# SW_S_12.net
KiCad netlist of a schematic drawn in Altium Designer
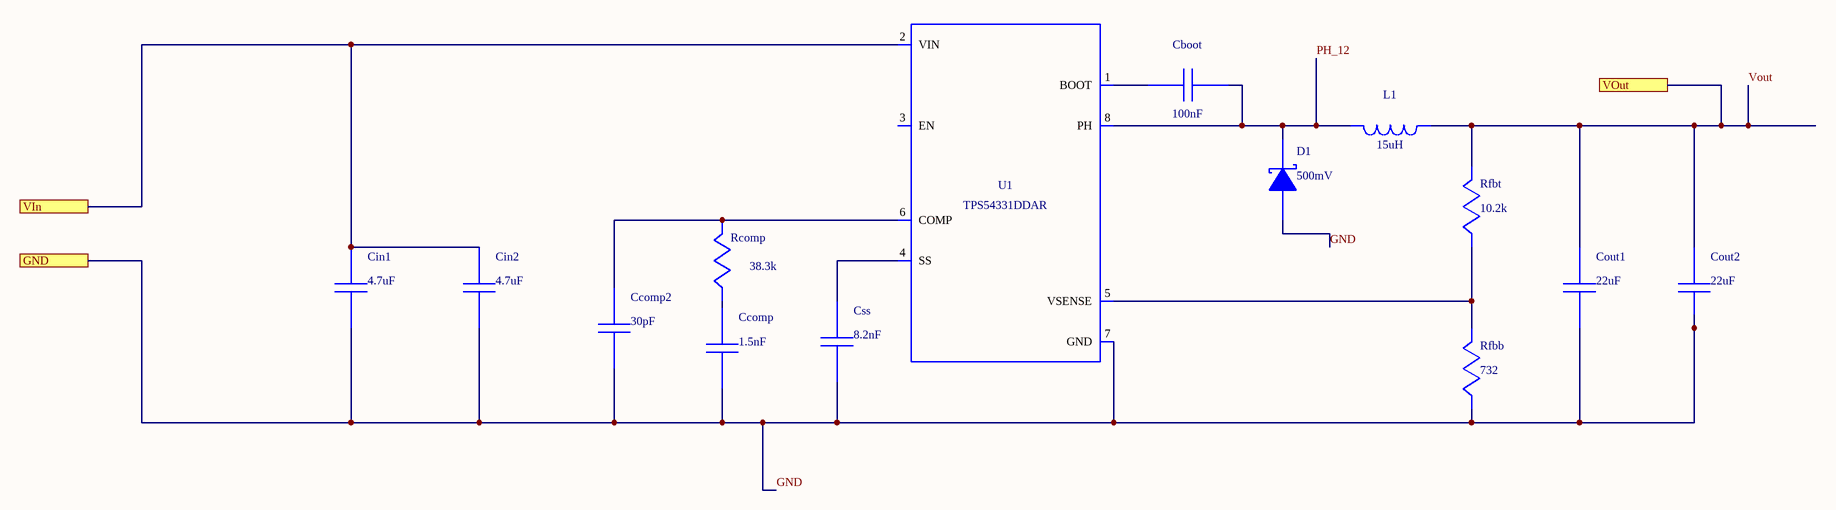
[diagram p0: SW_S_12.SchDoc]

(export (version "E")
  (design (tool "Eeschema 10.0.6"))
  (components
    (comp (ref "Cboot")
      (value "100nF")
      (footprint "1608[0603]")
      (description "C1608X7R1E104K")
      (libsource (lib "TI WEBENCH") (part "Cboot"))
    )
    (comp (ref "Ccomp")
      (value "1.5nF")
      (footprint "6-0805_M")
      (description "CC0805KRX7R9BB15")
      (fields (field (name "MANUFACTURER PART NUMBER") "CC0805KRX7R9BB152"))
      (libsource (lib "TI WEBENCH") (part "Ccomp"))
    )
    (comp (ref "Ccomp2")
      (value "30pF")
      (footprint "6-0805_M")
      (description "CL21C300JBANNNC")
      (libsource (lib "TI WEBENCH") (part "Ccomp2"))
    )
    (comp (ref "Cin1")
      (value "4.7uF")
      (footprint "C1210_M")
      (description "GRM32ER71H475KA8")
      (fields (field (name "MANUFACTURER PART NUMBER") "GRM32ER71H475KA88L"))
      (libsource (lib "TI WEBENCH") (part "Cin"))
    )
    (comp (ref "Cin2")
      (value "4.7uF")
      (footprint "C1210_M")
      (description "GRM32ER71H475KA8")
      (fields (field (name "MANUFACTURER PART NUMBER") "GRM32ER71H475KA88L"))
      (libsource (lib "TI WEBENCH") (part "Cin"))
    )
    (comp (ref "Cout1")
      (value "22uF")
      (footprint "C1210_M")
      (description "GRM32ER61E226KE1")
      (fields (field (name "MANUFACTURER PART NUMBER") "GRM32ER61E226KE15L"))
      (libsource (lib "TI WEBENCH") (part "Cout"))
    )
    (comp (ref "Cout2")
      (value "22uF")
      (footprint "C1210_M")
      (description "GRM32ER61E226KE1")
      (fields (field (name "MANUFACTURER PART NUMBER") "GRM32ER61E226KE15L"))
      (libsource (lib "TI WEBENCH") (part "Cout"))
    )
    (comp (ref "Css")
      (value "8.2nF")
      (footprint "1608[0603]")
      (description "GRM188R71E822KA0")
      (fields (field (name "MANUFACTURER PART NUMBER") "GRM188R71E822KA01D"))
      (libsource (lib "TI WEBENCH") (part "Css"))
    )
    (comp (ref "D1")
      (value "500mV")
      (footprint "SMA Diode Package")
      (description "B340A-13-F")
      (libsource (lib "TI WEBENCH") (part "D1"))
    )
    (comp (ref "L1")
      (value "15uH")
      (footprint "SRR1260")
      (description "SRR1260-150M")
      (libsource (lib "TI WEBENCH") (part "L1"))
    )
    (comp (ref "Rcomp")
      (value "38.3k")
      (footprint "6-0805_M")
      (description "CRCW080538K3FKEA")
      (libsource (lib "TI WEBENCH") (part "Rcomp"))
    )
    (comp (ref "Rfbb")
      (value "732")
      (footprint "6-0805_M")
      (description "CRCW0805732RFKEA")
      (libsource (lib "TI WEBENCH") (part "Rfbb"))
    )
    (comp (ref "Rfbt")
      (value "10.2k")
      (footprint "6-0805_M")
      (description "CRCW080510K2FKEA")
      (libsource (lib "TI WEBENCH") (part "Rfbt"))
    )
    (comp (ref "U1")
      (value "TPS54331DDAR")
      (footprint "TI-D8_N")
      (fields (field (name "PACKAGEREFERENCE") "TPS54331DDAR"))
      (libsource (lib "TI WEBENCH") (part "U1"))
    )
  )
  (nets
    (net (code "1") (name "/GND") (class "Default")
      (node (ref "Ccomp") (pin "2") (pinfunction "2_2") (pintype "passive"))
      (node (ref "Ccomp2") (pin "2") (pinfunction "2_2") (pintype "passive"))
      (node (ref "Cin1") (pin "2") (pinfunction "2_2") (pintype "passive"))
      (node (ref "Cin2") (pin "2") (pinfunction "2_2") (pintype "passive"))
      (node (ref "Cout1") (pin "2") (pinfunction "2_2") (pintype "passive"))
      (node (ref "Cout2") (pin "2") (pinfunction "2_2") (pintype "passive"))
      (node (ref "Css") (pin "2") (pinfunction "2_2") (pintype "passive"))
      (node (ref "D1") (pin "2") (pinfunction "A_2") (pintype "passive"))
      (node (ref "Rfbb") (pin "2") (pinfunction "2_2") (pintype "passive"))
      (node (ref "U1") (pin "7") (pinfunction "GND_7") (pintype "passive"))
    )
    (net (code "2") (name "/PH_12") (class "Default")
      (node (ref "Cboot") (pin "2") (pinfunction "2_2") (pintype "passive"))
      (node (ref "D1") (pin "1") (pinfunction "K_1") (pintype "passive"))
      (node (ref "L1") (pin "1") (pinfunction "1_1") (pintype "passive"))
      (node (ref "U1") (pin "8") (pinfunction "PH_8") (pintype "passive"))
    )
    (net (code "3") (name "/VIn") (class "Default")
      (node (ref "Cin1") (pin "1") (pinfunction "1_1") (pintype "passive"))
      (node (ref "Cin2") (pin "1") (pinfunction "1_1") (pintype "passive"))
      (node (ref "U1") (pin "2") (pinfunction "VIN_2") (pintype "passive"))
    )
    (net (code "4") (name "/Vout") (class "Default")
      (node (ref "Cout1") (pin "1") (pinfunction "1_1") (pintype "passive"))
      (node (ref "Cout2") (pin "1") (pinfunction "1_1") (pintype "passive"))
      (node (ref "L1") (pin "2") (pinfunction "2_2") (pintype "passive"))
      (node (ref "Rfbt") (pin "1") (pinfunction "1_1") (pintype "passive"))
    )
    (net (code "5") (name "Net-(Ccomp-Pad1)") (class "Default")
      (node (ref "Ccomp") (pin "1") (pinfunction "1_1") (pintype "passive"))
      (node (ref "Rcomp") (pin "2") (pinfunction "2_2") (pintype "passive"))
    )
    (net (code "6") (name "Net-(U1-BOOT)") (class "Default")
      (node (ref "Cboot") (pin "1") (pinfunction "1_1") (pintype "passive"))
      (node (ref "U1") (pin "1") (pinfunction "BOOT_1") (pintype "passive"))
    )
    (net (code "7") (name "Net-(U1-COMP)") (class "Default")
      (node (ref "Ccomp2") (pin "1") (pinfunction "1_1") (pintype "passive"))
      (node (ref "Rcomp") (pin "1") (pinfunction "1_1") (pintype "passive"))
      (node (ref "U1") (pin "6") (pinfunction "COMP_6") (pintype "passive"))
    )
    (net (code "8") (name "Net-(U1-SS)") (class "Default")
      (node (ref "Css") (pin "1") (pinfunction "1_1") (pintype "passive"))
      (node (ref "U1") (pin "4") (pinfunction "SS_4") (pintype "passive"))
    )
    (net (code "9") (name "Net-(U1-VSENSE)") (class "Default")
      (node (ref "Rfbb") (pin "1") (pinfunction "1_1") (pintype "passive"))
      (node (ref "Rfbt") (pin "2") (pinfunction "2_2") (pintype "passive"))
      (node (ref "U1") (pin "5") (pinfunction "VSENSE_5") (pintype "passive"))
    )
    (net (code "10") (name "unconnected-(U1-EN-Pad3)") (class "Default")
      (node (ref "U1") (pin "3") (pinfunction "EN_3") (pintype "passive"))
    )
  )
)
